# DIDV_-_Conector_DIDV_BEEB.net
KiCad netlist of a schematic drawn in EAGLE
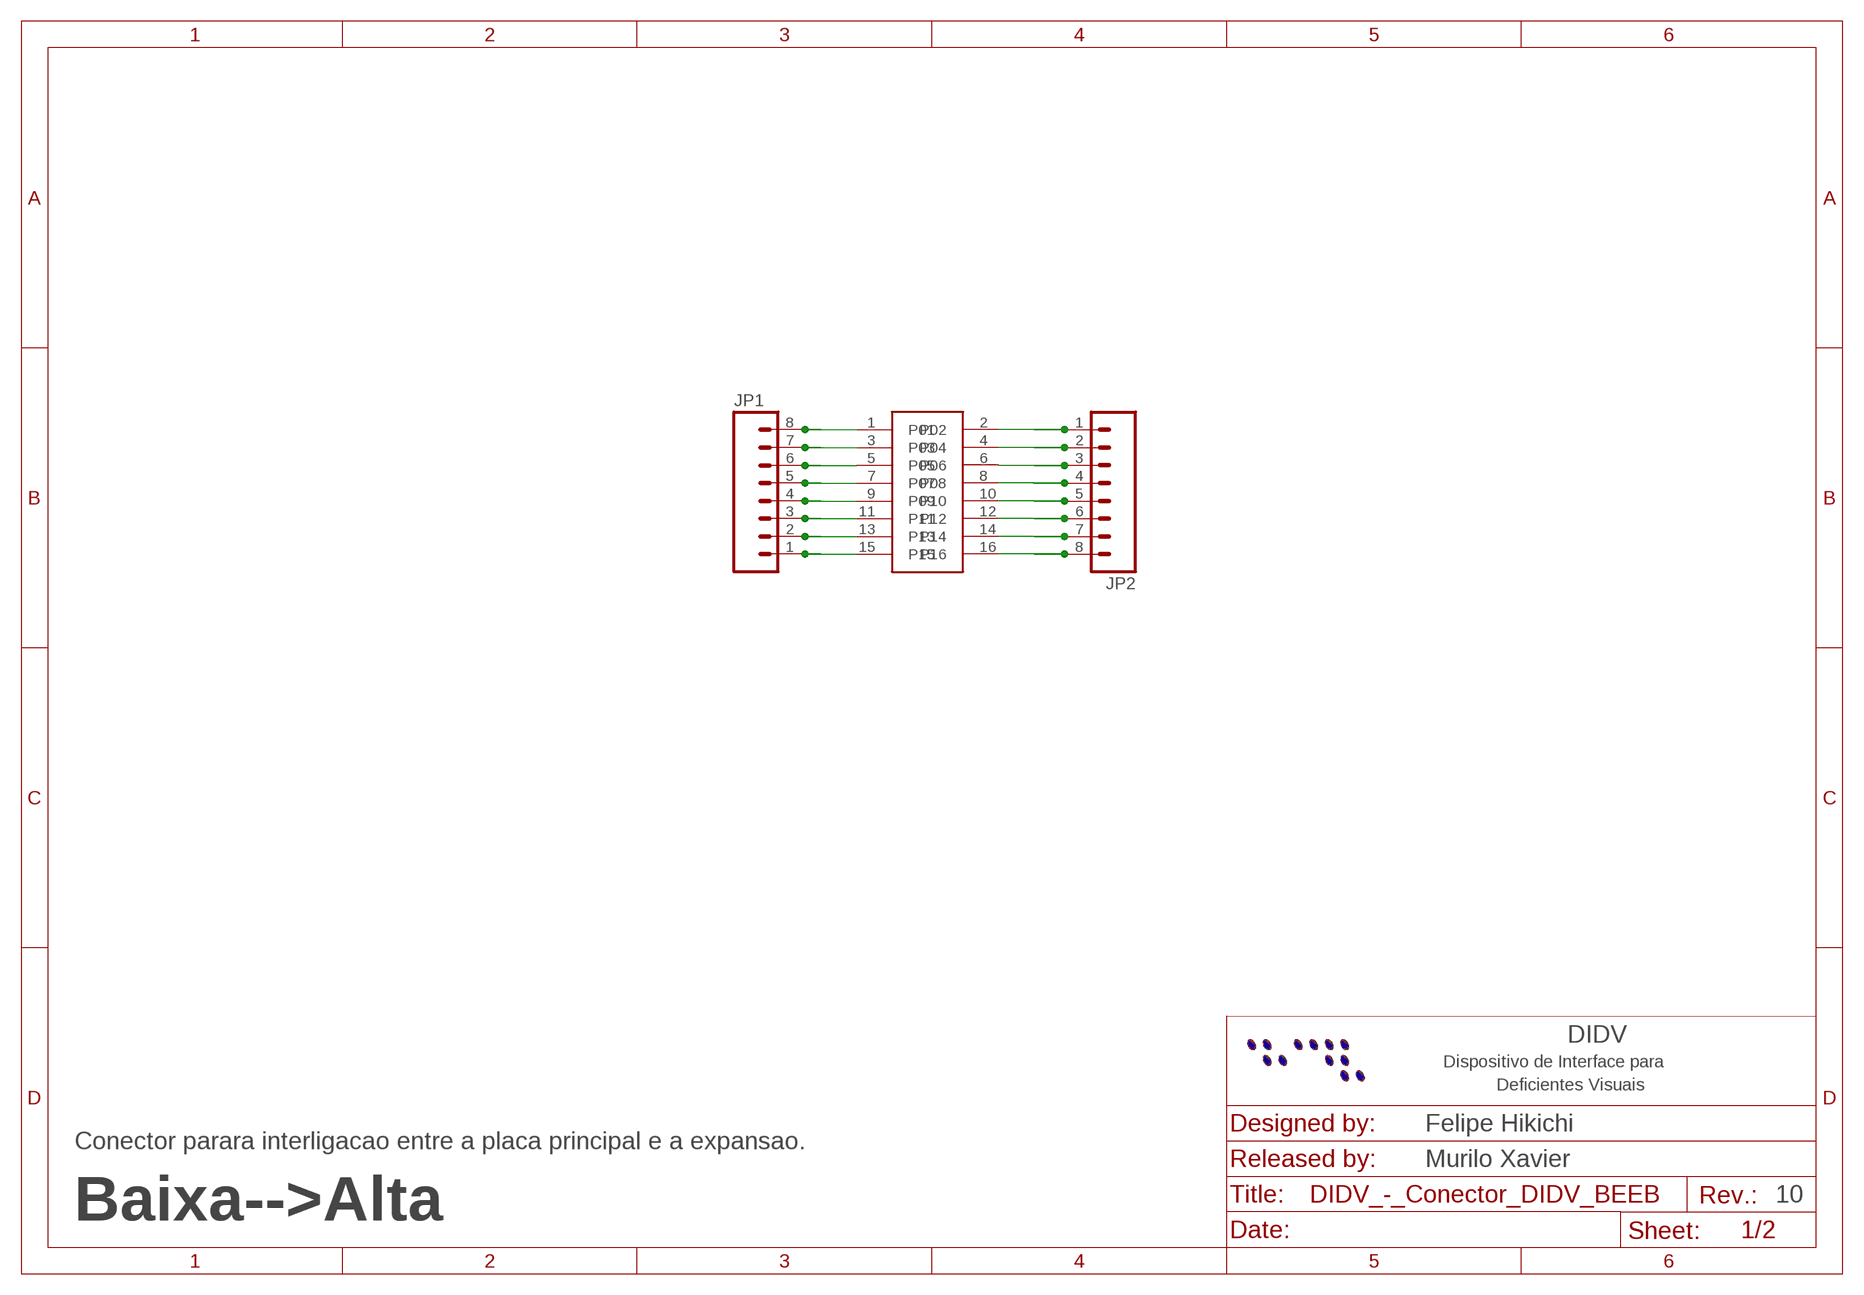
[diagram p0: schematic, sheet 1]
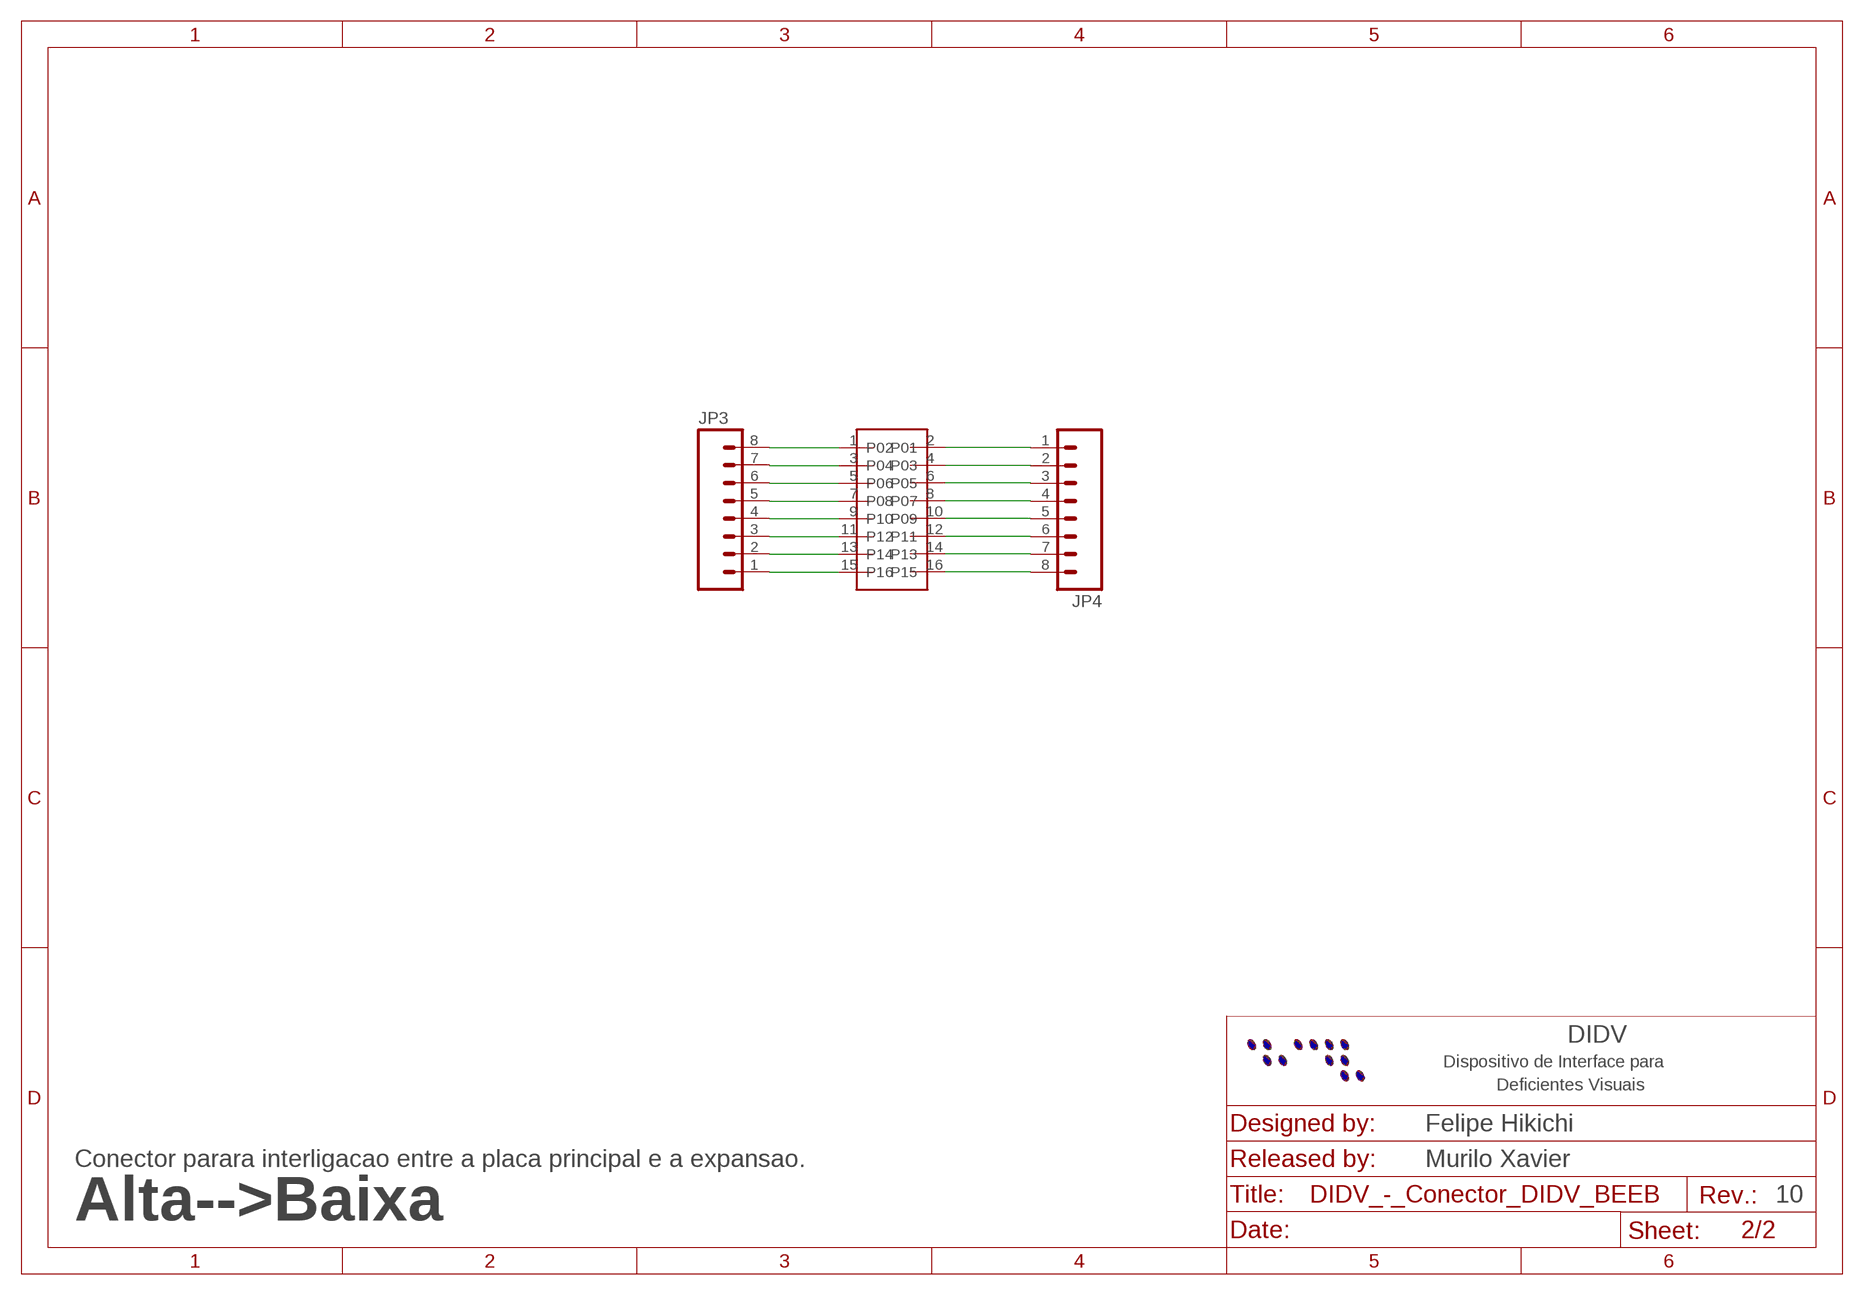
[diagram p1: schematic, sheet 2]

(export (version "E")
  (design (tool "Eeschema 10.0.6"))
  (components
    (comp (ref "JP1")
      (value "M08LONGPADS")
      (footprint "eagle-import:1X08_LONGPADS")
      (libsource (lib "eagle-import") (part "M08LONGPADS"))
    )
    (comp (ref "JP2")
      (value "M08LONGPADS")
      (footprint "eagle-import:1X08_LONGPADS")
      (libsource (lib "eagle-import") (part "M08LONGPADS"))
    )
    (comp (ref "X1")
      (value "SMDTOP-16")
      (footprint "eagle-import:SMDTOP16")
      (libsource (lib "eagle-import") (part "con-iriso2_SMDTOP-16"))
    )
    (comp (ref "JP3")
      (value "M08LONGPADS")
      (footprint "eagle-import:1X08_LONGPADS")
      (libsource (lib "eagle-import") (part "M08LONGPADS"))
    )
    (comp (ref "JP4")
      (value "M08LONGPADS")
      (footprint "eagle-import:1X08_LONGPADS")
      (libsource (lib "eagle-import") (part "M08LONGPADS"))
    )
    (comp (ref "X2")
      (value "SMDTOP-16")
      (footprint "eagle-import:SMDTOP16")
      (libsource (lib "eagle-import") (part "SMDTOP-16"))
    )
  )
  (nets
    (net (code "1") (name "Net-(X1-P01)") (class "Default")
      (node (ref "JP1") (pin "8") (pinfunction "8_8") (pintype "passive"))
      (node (ref "X1") (pin "1") (pinfunction "P01_1") (pintype "bidirectional"))
    )
    (net (code "2") (name "Net-(X1-P02)") (class "Default")
      (node (ref "JP2") (pin "1") (pinfunction "1_1") (pintype "passive"))
      (node (ref "X1") (pin "2") (pinfunction "P02_2") (pintype "bidirectional"))
    )
    (net (code "3") (name "Net-(X1-P03)") (class "Default")
      (node (ref "JP1") (pin "7") (pinfunction "7_7") (pintype "passive"))
      (node (ref "X1") (pin "3") (pinfunction "P03_3") (pintype "bidirectional"))
    )
    (net (code "4") (name "Net-(X1-P04)") (class "Default")
      (node (ref "JP2") (pin "2") (pinfunction "2_2") (pintype "passive"))
      (node (ref "X1") (pin "4") (pinfunction "P04_4") (pintype "bidirectional"))
    )
    (net (code "5") (name "Net-(X1-P05)") (class "Default")
      (node (ref "JP1") (pin "6") (pinfunction "6_6") (pintype "passive"))
      (node (ref "X1") (pin "5") (pinfunction "P05_5") (pintype "bidirectional"))
    )
    (net (code "6") (name "Net-(X1-P06)") (class "Default")
      (node (ref "JP2") (pin "3") (pinfunction "3_3") (pintype "passive"))
      (node (ref "X1") (pin "6") (pinfunction "P06_6") (pintype "bidirectional"))
    )
    (net (code "7") (name "Net-(X1-P07)") (class "Default")
      (node (ref "JP1") (pin "5") (pinfunction "5_5") (pintype "passive"))
      (node (ref "X1") (pin "7") (pinfunction "P07_7") (pintype "bidirectional"))
    )
    (net (code "8") (name "Net-(X1-P08)") (class "Default")
      (node (ref "JP2") (pin "4") (pinfunction "4_4") (pintype "passive"))
      (node (ref "X1") (pin "8") (pinfunction "P08_8") (pintype "bidirectional"))
    )
    (net (code "9") (name "Net-(X1-P09)") (class "Default")
      (node (ref "JP1") (pin "4") (pinfunction "4_4") (pintype "passive"))
      (node (ref "X1") (pin "9") (pinfunction "P09_9") (pintype "bidirectional"))
    )
    (net (code "10") (name "Net-(X1-P10)") (class "Default")
      (node (ref "JP2") (pin "5") (pinfunction "5_5") (pintype "passive"))
      (node (ref "X1") (pin "10") (pinfunction "P10_10") (pintype "bidirectional"))
    )
    (net (code "11") (name "Net-(X1-P11)") (class "Default")
      (node (ref "JP1") (pin "3") (pinfunction "3_3") (pintype "passive"))
      (node (ref "X1") (pin "11") (pinfunction "P11_11") (pintype "bidirectional"))
    )
    (net (code "12") (name "Net-(X1-P12)") (class "Default")
      (node (ref "JP2") (pin "6") (pinfunction "6_6") (pintype "passive"))
      (node (ref "X1") (pin "12") (pinfunction "P12_12") (pintype "bidirectional"))
    )
    (net (code "13") (name "Net-(X1-P13)") (class "Default")
      (node (ref "JP1") (pin "2") (pinfunction "2_2") (pintype "passive"))
      (node (ref "X1") (pin "13") (pinfunction "P13_13") (pintype "bidirectional"))
    )
    (net (code "14") (name "Net-(X1-P14)") (class "Default")
      (node (ref "JP2") (pin "7") (pinfunction "7_7") (pintype "passive"))
      (node (ref "X1") (pin "14") (pinfunction "P14_14") (pintype "bidirectional"))
    )
    (net (code "15") (name "Net-(X1-P15)") (class "Default")
      (node (ref "JP1") (pin "1") (pinfunction "1_1") (pintype "passive"))
      (node (ref "X1") (pin "15") (pinfunction "P15_15") (pintype "bidirectional"))
    )
    (net (code "16") (name "Net-(X1-P16)") (class "Default")
      (node (ref "JP2") (pin "8") (pinfunction "8_8") (pintype "passive"))
      (node (ref "X1") (pin "16") (pinfunction "P16_16") (pintype "bidirectional"))
    )
    (net (code "17") (name "Net-(X2-P01)") (class "Default")
      (node (ref "JP3") (pin "8") (pinfunction "8_8") (pintype "passive"))
      (node (ref "X2") (pin "1") (pinfunction "P01_1") (pintype "bidirectional"))
    )
    (net (code "18") (name "Net-(X2-P02)") (class "Default")
      (node (ref "JP4") (pin "1") (pinfunction "1_1") (pintype "passive"))
      (node (ref "X2") (pin "2") (pinfunction "P02_2") (pintype "bidirectional"))
    )
    (net (code "19") (name "Net-(X2-P03)") (class "Default")
      (node (ref "JP3") (pin "7") (pinfunction "7_7") (pintype "passive"))
      (node (ref "X2") (pin "3") (pinfunction "P03_3") (pintype "bidirectional"))
    )
    (net (code "20") (name "Net-(X2-P04)") (class "Default")
      (node (ref "JP4") (pin "2") (pinfunction "2_2") (pintype "passive"))
      (node (ref "X2") (pin "4") (pinfunction "P04_4") (pintype "bidirectional"))
    )
    (net (code "21") (name "Net-(X2-P05)") (class "Default")
      (node (ref "JP3") (pin "6") (pinfunction "6_6") (pintype "passive"))
      (node (ref "X2") (pin "5") (pinfunction "P05_5") (pintype "bidirectional"))
    )
    (net (code "22") (name "Net-(X2-P06)") (class "Default")
      (node (ref "JP4") (pin "3") (pinfunction "3_3") (pintype "passive"))
      (node (ref "X2") (pin "6") (pinfunction "P06_6") (pintype "bidirectional"))
    )
    (net (code "23") (name "Net-(X2-P07)") (class "Default")
      (node (ref "JP3") (pin "5") (pinfunction "5_5") (pintype "passive"))
      (node (ref "X2") (pin "7") (pinfunction "P07_7") (pintype "bidirectional"))
    )
    (net (code "24") (name "Net-(X2-P08)") (class "Default")
      (node (ref "JP4") (pin "4") (pinfunction "4_4") (pintype "passive"))
      (node (ref "X2") (pin "8") (pinfunction "P08_8") (pintype "bidirectional"))
    )
    (net (code "25") (name "Net-(X2-P09)") (class "Default")
      (node (ref "JP3") (pin "4") (pinfunction "4_4") (pintype "passive"))
      (node (ref "X2") (pin "9") (pinfunction "P09_9") (pintype "bidirectional"))
    )
    (net (code "26") (name "Net-(X2-P10)") (class "Default")
      (node (ref "JP4") (pin "5") (pinfunction "5_5") (pintype "passive"))
      (node (ref "X2") (pin "10") (pinfunction "P10_10") (pintype "bidirectional"))
    )
    (net (code "27") (name "Net-(X2-P11)") (class "Default")
      (node (ref "JP3") (pin "3") (pinfunction "3_3") (pintype "passive"))
      (node (ref "X2") (pin "11") (pinfunction "P11_11") (pintype "bidirectional"))
    )
    (net (code "28") (name "Net-(X2-P12)") (class "Default")
      (node (ref "JP4") (pin "6") (pinfunction "6_6") (pintype "passive"))
      (node (ref "X2") (pin "12") (pinfunction "P12_12") (pintype "bidirectional"))
    )
    (net (code "29") (name "Net-(X2-P13)") (class "Default")
      (node (ref "JP3") (pin "2") (pinfunction "2_2") (pintype "passive"))
      (node (ref "X2") (pin "13") (pinfunction "P13_13") (pintype "bidirectional"))
    )
    (net (code "30") (name "Net-(X2-P14)") (class "Default")
      (node (ref "JP4") (pin "7") (pinfunction "7_7") (pintype "passive"))
      (node (ref "X2") (pin "14") (pinfunction "P14_14") (pintype "bidirectional"))
    )
    (net (code "31") (name "Net-(X2-P15)") (class "Default")
      (node (ref "JP3") (pin "1") (pinfunction "1_1") (pintype "passive"))
      (node (ref "X2") (pin "15") (pinfunction "P15_15") (pintype "bidirectional"))
    )
    (net (code "32") (name "Net-(X2-P16)") (class "Default")
      (node (ref "JP4") (pin "8") (pinfunction "8_8") (pintype "passive"))
      (node (ref "X2") (pin "16") (pinfunction "P16_16") (pintype "bidirectional"))
    )
  )
)
